# ct_switching.net
KiCad netlist of a schematic drawn in Altium Designer
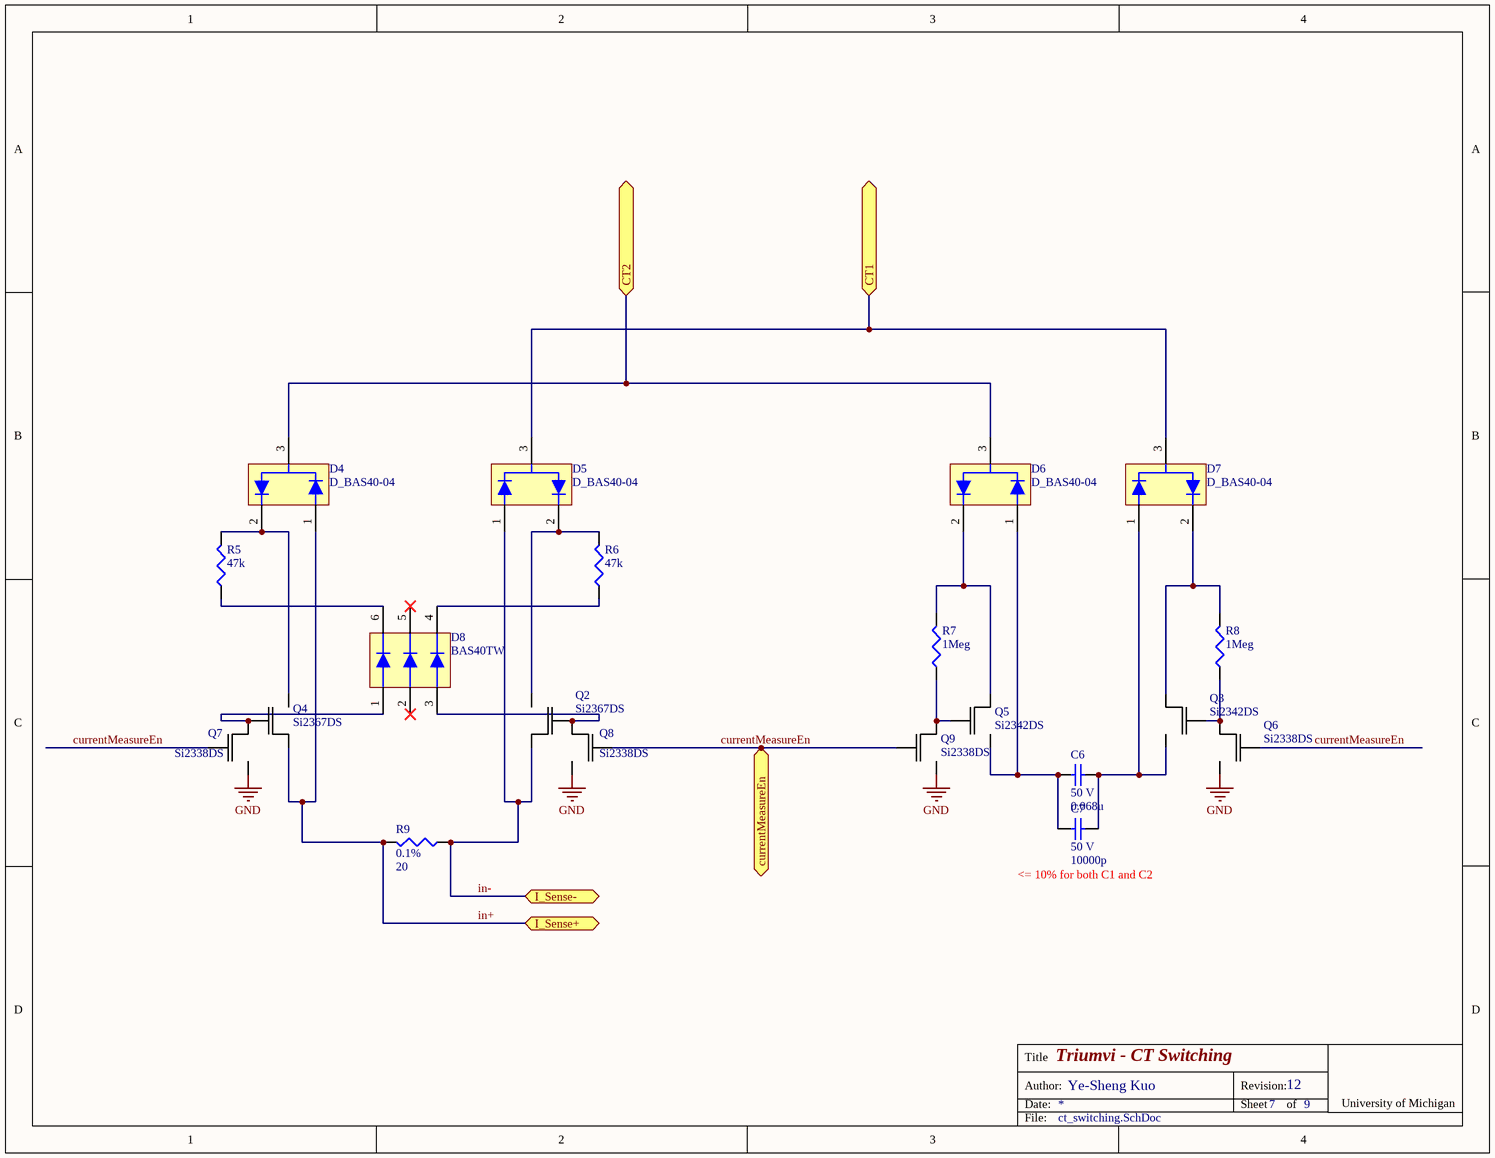
[diagram p0: ct_switching.SchDoc]

(export (version "E")
  (design (tool "Eeschema 10.0.6"))
  (components
    (comp (ref "C6")
      (value "0.068u")
      (footprint "0603")
      (description "0.068µF ±10% 50V Ceramic Capacitor X7R 0603")
      (fields
        (field (name "TOLERANCE") "10%")
        (field (name "VOLTAGE RATED") "50 V")
        (field (name "MANUFACTURER PART NUMBER") "C0603C683K5RACTU")
      )
      (libsource (lib "capacitors") (part "C0603C683K5RACTU"))
    )
    (comp (ref "C7")
      (value "10000p")
      (footprint "0603")
      (description "10000pF ±5% 50V Ceramic Capacitor X7R 0603")
      (fields
        (field (name "TOLERANCE") "5%")
        (field (name "VOLTAGE RATED") "50 V")
        (field (name "MANUFACTURER PART NUMBER") "C0603C103J5RACTU")
      )
      (libsource (lib "capacitors") (part "C0603C103J5RACTU"))
    )
    (comp (ref "D4")
      (value "D_BAS40-04")
      (footprint "SOT23-3")
      (description "SURFACE MOUNT SCHOTTKY BARRIER DIODE")
      (libsource (lib "diodes") (part "D_BAS40-04"))
    )
    (comp (ref "D5")
      (value "D_BAS40-04")
      (footprint "SOT23-3")
      (description "SURFACE MOUNT SCHOTTKY BARRIER DIODE")
      (libsource (lib "") (part "D_BAS40-04_1"))
    )
    (comp (ref "D6")
      (value "D_BAS40-04")
      (footprint "SOT23-3")
      (description "SURFACE MOUNT SCHOTTKY BARRIER DIODE")
      (libsource (lib "diodes") (part "D_BAS40-04"))
    )
    (comp (ref "D7")
      (value "D_BAS40-04")
      (footprint "SOT23-3")
      (description "SURFACE MOUNT SCHOTTKY BARRIER DIODE")
      (libsource (lib "") (part "D_BAS40-04_1"))
    )
    (comp (ref "D8")
      (value "BAS40TW")
      (footprint "SOT-363")
      (description "SURFACE MOUNT SCHOTTKY BARRIER DIODE ARRAYS")
      (libsource (lib "diodes") (part "D_BAS40TW"))
    )
    (comp (ref "Q2")
      (value "Si2367DS")
      (footprint "SOT23-3")
      (description "P-Channel 20 V (D-S) MOSFET")
      (libsource (lib "transistors") (part "Si2367DS"))
    )
    (comp (ref "Q3")
      (value "Si2342DS")
      (footprint "SOT23-3")
      (description "N-Channel 8 V (D-S) MOSFET")
      (libsource (lib "transistors") (part "Si2342DS"))
    )
    (comp (ref "Q4")
      (value "Si2367DS")
      (footprint "SOT23-3")
      (description "P-Channel 20 V (D-S) MOSFET")
      (libsource (lib "transistors") (part "Si2367DS"))
    )
    (comp (ref "Q5")
      (value "Si2342DS")
      (footprint "SOT23-3")
      (description "N-Channel 8 V (D-S) MOSFET")
      (libsource (lib "transistors") (part "Si2342DS"))
    )
    (comp (ref "Q6")
      (value "Si2338DS")
      (footprint "SOT23-3")
      (description "N-Channel 30 V (D-S) MOSFET")
      (libsource (lib "transistors") (part "Si2338DS"))
    )
    (comp (ref "Q7")
      (value "Si2338DS")
      (footprint "SOT23-3")
      (description "N-Channel 30 V (D-S) MOSFET")
      (libsource (lib "transistors") (part "Si2338DS"))
    )
    (comp (ref "Q8")
      (value "Si2338DS")
      (footprint "SOT23-3")
      (description "N-Channel 30 V (D-S) MOSFET")
      (libsource (lib "transistors") (part "Si2338DS"))
    )
    (comp (ref "Q9")
      (value "Si2338DS")
      (footprint "SOT23-3")
      (description "N-Channel 30 V (D-S) MOSFET")
      (libsource (lib "transistors") (part "Si2338DS"))
    )
    (comp (ref "R5")
      (value "47k")
      (footprint "0402")
      (description "RES SMD 47K OHM 1% 1/16W 0402")
      (fields (field (name "TOLERANCE") "1%") (field (name "POWER") "1/16 W"))
      (libsource (lib "resistors") (part "CRCW040247K0FKED"))
    )
    (comp (ref "R6")
      (value "47k")
      (footprint "0402")
      (description "RES SMD 47K OHM 1% 1/16W 0402")
      (fields (field (name "TOLERANCE") "1%") (field (name "POWER") "1/16 W"))
      (libsource (lib "resistors") (part "CRCW040247K0FKED"))
    )
    (comp (ref "R7")
      (value "1Meg")
      (footprint "0402")
      (description "RES SMD 1M OHM 1% 1/16W 0402")
      (fields (field (name "TOLERANCE") "1%") (field (name "POWER") "1/16 W"))
      (libsource (lib "resistors") (part "CRCW04021M00FKED"))
    )
    (comp (ref "R8")
      (value "1Meg")
      (footprint "0402")
      (description "RES SMD 1M OHM 1% 1/16W 0402")
      (fields (field (name "TOLERANCE") "1%") (field (name "POWER") "1/16 W"))
      (libsource (lib "resistors") (part "CRCW04021M00FKED"))
    )
    (comp (ref "R9")
      (value "20")
      (footprint "0805")
      (description "RES SMD 20 OHM 0.1% 1/5W 0805")
      (fields
        (field (name "MANUFACTURER PART NUMBER") "RTAN0805BKE20R0")
        (field (name "MANUFACTURER") "Stackpole Electronics Inc.")
        (field (name "TOLERANCE") "0.1%")
      )
      (libsource (lib "resistors") (part "RTAN0805BKE20R0"))
    )
  )
  (nets
    (net (code "1") (name "/CT1") (class "Default")
      (node (ref "D5") (pin "3") (pinfunction "3_3") (pintype "passive"))
      (node (ref "D7") (pin "3") (pinfunction "3_3") (pintype "passive"))
    )
    (net (code "2") (name "/CT2") (class "Default")
      (node (ref "D4") (pin "3") (pinfunction "3_3") (pintype "passive"))
      (node (ref "D6") (pin "3") (pinfunction "3_3") (pintype "passive"))
    )
    (net (code "3") (name "/currentMeasureEn") (class "Default")
      (node (ref "Q6") (pin "1") (pinfunction "G_1") (pintype "passive"))
      (node (ref "Q7") (pin "1") (pinfunction "G_1") (pintype "passive"))
      (node (ref "Q8") (pin "1") (pinfunction "G_1") (pintype "passive"))
      (node (ref "Q9") (pin "1") (pinfunction "G_1") (pintype "passive"))
    )
    (net (code "4") (name "/in+") (class "Default")
      (node (ref "D4") (pin "1") (pinfunction "1_1") (pintype "passive"))
      (node (ref "Q4") (pin "3") (pinfunction "D_3") (pintype "passive"))
      (node (ref "R9") (pin "1") (pintype "passive"))
    )
    (net (code "5") (name "/in-") (class "Default")
      (node (ref "D5") (pin "1") (pinfunction "1_1") (pintype "passive"))
      (node (ref "Q2") (pin "3") (pinfunction "D_3") (pintype "passive"))
      (node (ref "R9") (pin "2") (pintype "passive"))
    )
    (net (code "6") (name "GND") (class "Default")
      (node (ref "Q6") (pin "2") (pinfunction "S_2") (pintype "passive"))
      (node (ref "Q7") (pin "2") (pinfunction "S_2") (pintype "passive"))
      (node (ref "Q8") (pin "2") (pinfunction "S_2") (pintype "passive"))
      (node (ref "Q9") (pin "2") (pinfunction "S_2") (pintype "passive"))
    )
    (net (code "7") (name "Net-(D8-Pad4)") (class "Default")
      (node (ref "D8") (pin "4") (pinfunction "4_4") (pintype "passive"))
      (node (ref "R6") (pin "2") (pintype "passive"))
    )
    (net (code "8") (name "Net-(D8-Pad6)") (class "Default")
      (node (ref "D8") (pin "6") (pinfunction "6_6") (pintype "passive"))
      (node (ref "R5") (pin "2") (pintype "passive"))
    )
    (net (code "9") (name "Net-(Q2-G)") (class "Default")
      (node (ref "D8") (pin "3") (pinfunction "3_3") (pintype "passive"))
      (node (ref "Q2") (pin "1") (pinfunction "G_1") (pintype "passive"))
      (node (ref "Q8") (pin "3") (pinfunction "D_3") (pintype "passive"))
    )
    (net (code "10") (name "Net-(Q2-S)") (class "Default")
      (node (ref "D5") (pin "2") (pinfunction "2_2") (pintype "passive"))
      (node (ref "Q2") (pin "2") (pinfunction "S_2") (pintype "passive"))
      (node (ref "R6") (pin "1") (pintype "passive"))
    )
    (net (code "11") (name "Net-(Q3-D)") (class "Default")
      (node (ref "D7") (pin "2") (pinfunction "2_2") (pintype "passive"))
      (node (ref "Q3") (pin "3") (pinfunction "D_3") (pintype "passive"))
      (node (ref "R8") (pin "1") (pintype "passive"))
    )
    (net (code "12") (name "Net-(Q3-G)") (class "Default")
      (node (ref "Q3") (pin "1") (pinfunction "G_1") (pintype "passive"))
      (node (ref "Q6") (pin "3") (pinfunction "D_3") (pintype "passive"))
      (node (ref "R8") (pin "2") (pintype "passive"))
    )
    (net (code "13") (name "Net-(Q3-S)") (class "Default")
      (node (ref "C6") (pin "2") (pintype "passive"))
      (node (ref "C7") (pin "2") (pintype "passive"))
      (node (ref "D7") (pin "1") (pinfunction "1_1") (pintype "passive"))
      (node (ref "Q3") (pin "2") (pinfunction "S_2") (pintype "passive"))
    )
    (net (code "14") (name "Net-(Q4-G)") (class "Default")
      (node (ref "D8") (pin "1") (pinfunction "1_1") (pintype "passive"))
      (node (ref "Q4") (pin "1") (pinfunction "G_1") (pintype "passive"))
      (node (ref "Q7") (pin "3") (pinfunction "D_3") (pintype "passive"))
    )
    (net (code "15") (name "Net-(Q4-S)") (class "Default")
      (node (ref "D4") (pin "2") (pinfunction "2_2") (pintype "passive"))
      (node (ref "Q4") (pin "2") (pinfunction "S_2") (pintype "passive"))
      (node (ref "R5") (pin "1") (pintype "passive"))
    )
    (net (code "16") (name "Net-(Q5-D)") (class "Default")
      (node (ref "D6") (pin "2") (pinfunction "2_2") (pintype "passive"))
      (node (ref "Q5") (pin "3") (pinfunction "D_3") (pintype "passive"))
      (node (ref "R7") (pin "1") (pintype "passive"))
    )
    (net (code "17") (name "Net-(Q5-G)") (class "Default")
      (node (ref "Q5") (pin "1") (pinfunction "G_1") (pintype "passive"))
      (node (ref "Q9") (pin "3") (pinfunction "D_3") (pintype "passive"))
      (node (ref "R7") (pin "2") (pintype "passive"))
    )
    (net (code "18") (name "Net-(Q5-S)") (class "Default")
      (node (ref "C6") (pin "1") (pintype "passive"))
      (node (ref "C7") (pin "1") (pintype "passive"))
      (node (ref "D6") (pin "1") (pinfunction "1_1") (pintype "passive"))
      (node (ref "Q5") (pin "2") (pinfunction "S_2") (pintype "passive"))
    )
    (net (code "19") (name "unconnected-(D8-Pad2)") (class "Default")
      (node (ref "D8") (pin "2") (pinfunction "2_2") (pintype "passive+no_connect"))
    )
    (net (code "20") (name "unconnected-(D8-Pad5)") (class "Default")
      (node (ref "D8") (pin "5") (pinfunction "5_5") (pintype "passive+no_connect"))
    )
  )
)
